# sch.net
KiCad netlist of a schematic drawn in Altium Designer
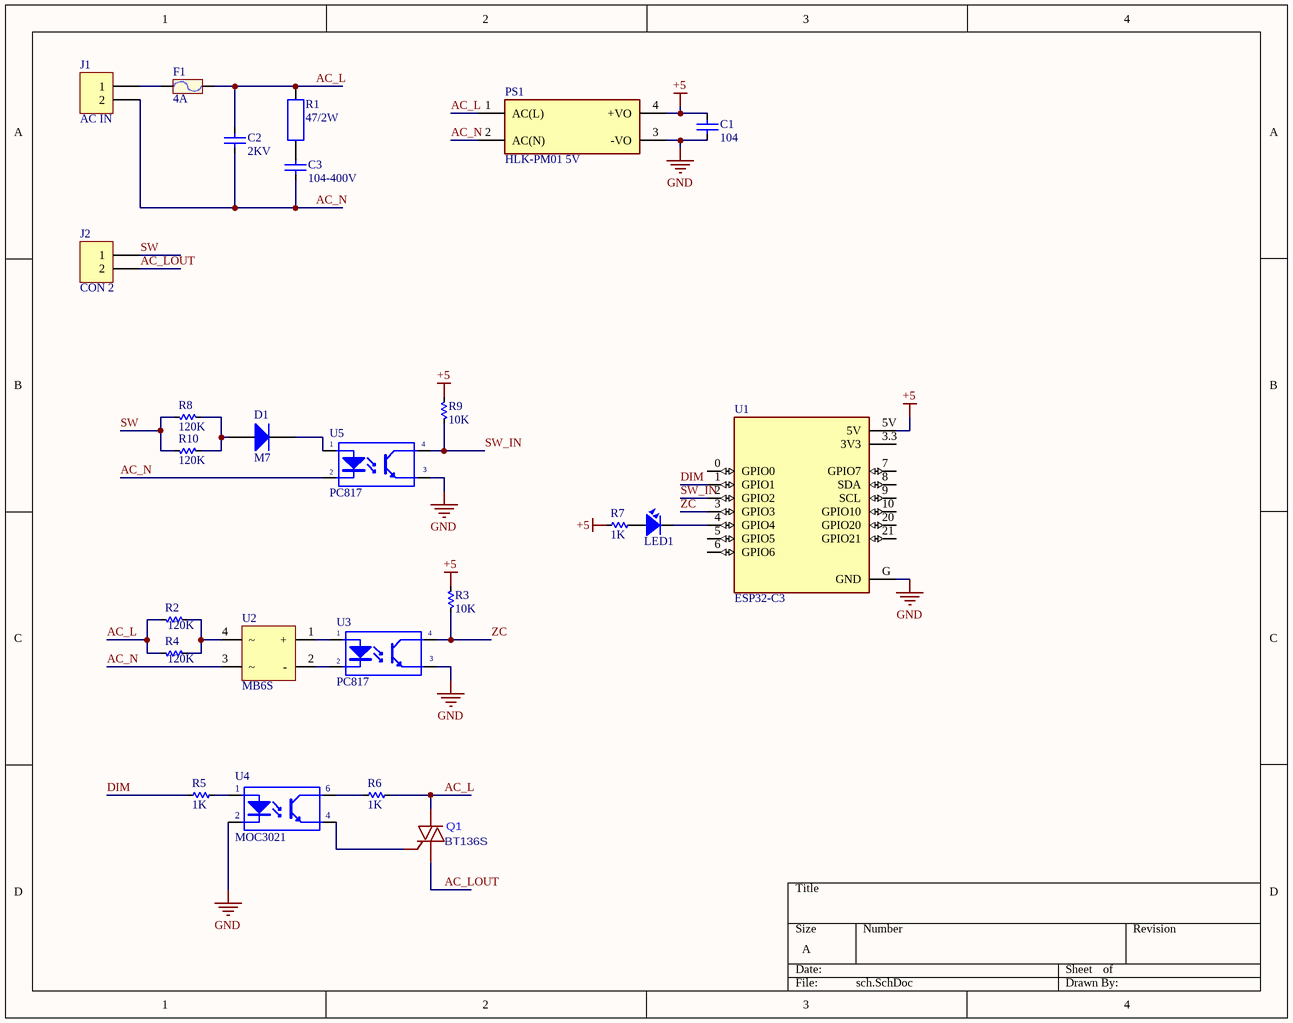
[diagram p0: sch.SchDoc]

(export (version "E")
  (design (tool "Eeschema 10.0.6"))
  (components
    (comp (ref "C1")
      (value "104")
      (footprint "cap 0805")
      (description "Capacitor")
      (libsource (lib "iuh-thuc-hanh") (part "CN"))
    )
    (comp (ref "C2")
      (value "2KV")
      (footprint "Cap 7.5mm")
      (description "Capacitor Ceramic 2KV")
      (libsource (lib "iuh-thuc-hanh") (part "Cap 103 2KV"))
    )
    (comp (ref "C3")
      (value "104-400V")
      (footprint "Cap 10mm")
      (description "Capacitor")
      (libsource (lib "iuh-thuc-hanh") (part "CN"))
    )
    (comp (ref "D1")
      (value "M7")
      (footprint "DIODE SMA")
      (description "Dán")
      (libsource (lib "Altium_Lib_by_KhueNguyenCreator") (part "Diode M7 ( 4007 )"))
    )
    (comp (ref "F1")
      (value "4A")
      (footprint "Fuse rectangular")
      (description "Fuse")
      (fields (field (name "DESIGNED BY") "VanDungEvn"))
      (libsource (lib "iuh-thuc-hanh") (part "Fuse"))
    )
    (comp (ref "J1")
      (value "AC IN")
      (footprint "CON 2 2EDG5.08 B")
      (description "CON2 KF terminal")
      (libsource (lib "iuh-thuc-hanh") (part "CON 2 EDG"))
    )
    (comp (ref "J2")
      (value "CON 2")
      (footprint "CON 2 2EDG5.08 B")
      (description "CON2 KF terminal")
      (libsource (lib "iuh-thuc-hanh") (part "CON 2 EDG"))
    )
    (comp (ref "LED1")
      (value "LED")
      (footprint "LED-0805-Blue")
      (libsource (lib "LIBRARY1") (part "LED SMD"))
    )
    (comp (ref "PS1")
      (value "HLK-PM01 5V")
      (footprint "CONV_HLK-PM01-3W")
      (description "220VAC to 5V")
      (libsource (lib "iuh-thuc-hanh") (part "CONV HLK-PM01"))
    )
    (comp (ref "Q1")
      (value "BT136S")
      (footprint "TO-252-3_L6.6-W6.1-P4.57-LS9.9-BR-CW")
      (libsource (lib "Altium_Lib_by_KhueNguyenCreator") (part "BT136-800E_C2901010"))
    )
    (comp (ref "R1")
      (value "47/2W")
      (footprint "R2WD")
      (description "Resistor 2W")
      (libsource (lib "iuh-thuc-hanh") (part "R2W"))
    )
    (comp (ref "R2")
      (value "120K")
      (footprint "RES-SMD-1210")
      (description "Resistor")
      (fields
        (field (name "MANUFACTURER") "Generic Components")
        (field (name "PUBLISHER") "Altium Hobart Technology Centre")
      )
      (libsource (lib "LIBRARY1") (part "Res-SMD"))
    )
    (comp (ref "R3")
      (value "10K")
      (footprint "RES-SMD-0805")
      (description "Resistor")
      (fields
        (field (name "MANUFACTURER") "Generic Components")
        (field (name "PUBLISHER") "Altium Hobart Technology Centre")
      )
      (libsource (lib "LIBRARY1") (part "Res-SMD"))
    )
    (comp (ref "R4")
      (value "120K")
      (footprint "RES-SMD-1210")
      (description "Resistor")
      (fields
        (field (name "MANUFACTURER") "Generic Components")
        (field (name "PUBLISHER") "Altium Hobart Technology Centre")
      )
      (libsource (lib "LIBRARY1") (part "Res-SMD"))
    )
    (comp (ref "R5")
      (value "1K")
      (footprint "RES-SMD-0805")
      (description "Resistor")
      (fields
        (field (name "MANUFACTURER") "Generic Components")
        (field (name "PUBLISHER") "Altium Hobart Technology Centre")
      )
      (libsource (lib "LIBRARY1") (part "Res-SMD"))
    )
    (comp (ref "R6")
      (value "1K")
      (footprint "RES-SMD-0805")
      (description "Resistor")
      (fields
        (field (name "MANUFACTURER") "Generic Components")
        (field (name "PUBLISHER") "Altium Hobart Technology Centre")
      )
      (libsource (lib "LIBRARY1") (part "Res-SMD"))
    )
    (comp (ref "R7")
      (value "1K")
      (footprint "RES-SMD-0805")
      (description "Resistor")
      (fields
        (field (name "MANUFACTURER") "Generic Components")
        (field (name "PUBLISHER") "Altium Hobart Technology Centre")
      )
      (libsource (lib "LIBRARY1") (part "Res-SMD"))
    )
    (comp (ref "R8")
      (value "120K")
      (footprint "RES-SMD-1210")
      (description "Resistor")
      (fields
        (field (name "MANUFACTURER") "Generic Components")
        (field (name "PUBLISHER") "Altium Hobart Technology Centre")
      )
      (libsource (lib "LIBRARY1") (part "Res-SMD"))
    )
    (comp (ref "R9")
      (value "10K")
      (footprint "RES-SMD-0805")
      (description "Resistor")
      (fields
        (field (name "MANUFACTURER") "Generic Components")
        (field (name "PUBLISHER") "Altium Hobart Technology Centre")
      )
      (libsource (lib "LIBRARY1") (part "Res-SMD"))
    )
    (comp (ref "R10")
      (value "120K")
      (footprint "RES-SMD-1210")
      (description "Resistor")
      (fields
        (field (name "MANUFACTURER") "Generic Components")
        (field (name "PUBLISHER") "Altium Hobart Technology Centre")
      )
      (libsource (lib "LIBRARY1") (part "Res-SMD"))
    )
    (comp (ref "U1")
      (value "ESP32-C3")
      (footprint "ESP32-C3-SMD")
      (libsource (lib "iuh-thuc-hanh") (part "ESP32-C3"))
    )
    (comp (ref "U2")
      (value "MB6S")
      (footprint "TO269AA")
      (description "Bridge Rectifier")
      (libsource (lib "iuh-thuc-hanh") (part "MB6S"))
    )
    (comp (ref "U3")
      (value "PC817")
      (footprint "SOP4")
      (description "Single Opto")
      (libsource (lib "Altium_Lib_by_KhueNguyenCreator") (part "OPTO PC817 SMD"))
    )
    (comp (ref "U4")
      (value "MOC3021")
      (footprint "SO6")
      (description "Single Opto")
      (libsource (lib "LIBRARY1") (part "MOC3021"))
    )
    (comp (ref "U5")
      (value "PC817")
      (footprint "SOP4")
      (description "Single Opto")
      (libsource (lib "Altium_Lib_by_KhueNguyenCreator") (part "OPTO PC817 SMD"))
    )
  )
  (nets
    (net (code "1") (name "+5") (class "Default")
      (node (ref "C1") (pin "1") (pinfunction "1_1") (pintype "passive"))
      (node (ref "PS1") (pin "4") (pinfunction "+VO_4") (pintype "power_in"))
      (node (ref "R3") (pin "1") (pinfunction "1_1") (pintype "passive"))
      (node (ref "R7") (pin "2") (pinfunction "2_2") (pintype "passive"))
      (node (ref "R9") (pin "1") (pinfunction "1_1") (pintype "passive"))
      (node (ref "U1") (pin "5V") (pinfunction "5V_5V") (pintype "power_in"))
    )
    (net (code "2") (name "/AC_L") (class "Default")
      (node (ref "C2") (pin "2") (pinfunction "2_2") (pintype "passive"))
      (node (ref "F1") (pin "2") (pinfunction "2_2") (pintype "passive"))
      (node (ref "PS1") (pin "1") (pinfunction "AC(L)_1") (pintype "power_in"))
      (node (ref "Q1") (pin "2") (pinfunction "T2_2") (pintype "passive"))
      (node (ref "R1") (pin "2") (pinfunction "2_2") (pintype "passive"))
      (node (ref "R2") (pin "1") (pinfunction "1_1") (pintype "passive"))
      (node (ref "R4") (pin "1") (pinfunction "1_1") (pintype "passive"))
      (node (ref "R6") (pin "1") (pinfunction "1_1") (pintype "passive"))
    )
    (net (code "3") (name "/AC_LOUT") (class "Default")
      (node (ref "J2") (pin "2") (pinfunction "2_2") (pintype "passive"))
      (node (ref "Q1") (pin "1") (pinfunction "T1_1") (pintype "passive"))
    )
    (net (code "4") (name "/AC_N") (class "Default")
      (node (ref "C2") (pin "1") (pinfunction "1_1") (pintype "passive"))
      (node (ref "C3") (pin "2") (pinfunction "2_2") (pintype "passive"))
      (node (ref "J1") (pin "2") (pinfunction "2_2") (pintype "passive"))
      (node (ref "PS1") (pin "2") (pinfunction "AC(N)_2") (pintype "power_in"))
      (node (ref "U2") (pin "3") (pinfunction "~_3") (pintype "passive"))
      (node (ref "U5") (pin "2") (pinfunction "K_2") (pintype "passive"))
    )
    (net (code "5") (name "/DIM") (class "Default")
      (node (ref "R5") (pin "2") (pinfunction "2_2") (pintype "passive"))
      (node (ref "U1") (pin "1") (pinfunction "GPIO1_1") (pintype "bidirectional"))
    )
    (net (code "6") (name "/SW") (class "Default")
      (node (ref "J2") (pin "1") (pinfunction "1_1") (pintype "passive"))
      (node (ref "R10") (pin "1") (pinfunction "1_1") (pintype "passive"))
      (node (ref "R8") (pin "1") (pinfunction "1_1") (pintype "passive"))
    )
    (net (code "7") (name "/SW_IN") (class "Default")
      (node (ref "R9") (pin "2") (pinfunction "2_2") (pintype "passive"))
      (node (ref "U1") (pin "2") (pinfunction "GPIO2_2") (pintype "bidirectional"))
      (node (ref "U5") (pin "4") (pinfunction "C_4") (pintype "passive"))
    )
    (net (code "8") (name "/ZC") (class "Default")
      (node (ref "R3") (pin "2") (pinfunction "2_2") (pintype "passive"))
      (node (ref "U1") (pin "3") (pinfunction "GPIO3_3") (pintype "bidirectional"))
      (node (ref "U3") (pin "4") (pinfunction "C_4") (pintype "passive"))
    )
    (net (code "9") (name "GND") (class "Default")
      (node (ref "C1") (pin "2") (pinfunction "2_2") (pintype "passive"))
      (node (ref "PS1") (pin "3") (pinfunction "-VO_3") (pintype "power_in"))
      (node (ref "U1") (pin "G") (pinfunction "GND_G") (pintype "power_in"))
      (node (ref "U3") (pin "3") (pinfunction "E_3") (pintype "passive"))
      (node (ref "U4") (pin "2") (pinfunction "K_2") (pintype "passive"))
      (node (ref "U5") (pin "3") (pinfunction "E_3") (pintype "passive"))
    )
    (net (code "10") (name "Net-(C3-Pad1)") (class "Default")
      (node (ref "C3") (pin "1") (pinfunction "1_1") (pintype "passive"))
      (node (ref "R1") (pin "1") (pinfunction "1_1") (pintype "passive"))
    )
    (net (code "11") (name "Net-(D1-A)") (class "Default")
      (node (ref "D1") (pin "1") (pinfunction "A_1") (pintype "passive"))
      (node (ref "R10") (pin "2") (pinfunction "2_2") (pintype "passive"))
      (node (ref "R8") (pin "2") (pinfunction "2_2") (pintype "passive"))
    )
    (net (code "12") (name "Net-(D1-K)") (class "Default")
      (node (ref "D1") (pin "2") (pinfunction "K_2") (pintype "passive"))
      (node (ref "U5") (pin "1") (pinfunction "A_1") (pintype "passive"))
    )
    (net (code "13") (name "Net-(F1-Pad1)") (class "Default")
      (node (ref "F1") (pin "1") (pinfunction "1_1") (pintype "passive"))
      (node (ref "J1") (pin "1") (pinfunction "1_1") (pintype "passive"))
    )
    (net (code "14") (name "Net-(LED1-Pad1)") (class "Default")
      (node (ref "LED1") (pin "1") (pinfunction "1_1") (pintype "passive"))
      (node (ref "R7") (pin "1") (pinfunction "1_1") (pintype "passive"))
    )
    (net (code "15") (name "Net-(Q1-G)") (class "Default")
      (node (ref "Q1") (pin "3") (pinfunction "G_3") (pintype "passive"))
      (node (ref "U4") (pin "4") (pinfunction "E_4") (pintype "passive"))
    )
    (net (code "16") (name "Net-(R2-Pad2)") (class "Default")
      (node (ref "R2") (pin "2") (pinfunction "2_2") (pintype "passive"))
      (node (ref "R4") (pin "2") (pinfunction "2_2") (pintype "passive"))
      (node (ref "U2") (pin "4") (pinfunction "~_4") (pintype "passive"))
    )
    (net (code "17") (name "Net-(U1-GPIO4)") (class "Default")
      (node (ref "LED1") (pin "2") (pinfunction "2_2") (pintype "passive"))
      (node (ref "U1") (pin "4") (pinfunction "GPIO4_4") (pintype "bidirectional"))
    )
    (net (code "18") (name "Net-(U2-+)") (class "Default")
      (node (ref "U2") (pin "1") (pinfunction "+_1") (pintype "passive"))
      (node (ref "U3") (pin "1") (pinfunction "A_1") (pintype "passive"))
    )
    (net (code "19") (name "Net-(U2--)") (class "Default")
      (node (ref "U2") (pin "2") (pinfunction "-_2") (pintype "passive"))
      (node (ref "U3") (pin "2") (pinfunction "K_2") (pintype "passive"))
    )
    (net (code "20") (name "Net-(U4-A)") (class "Default")
      (node (ref "R5") (pin "1") (pinfunction "1_1") (pintype "passive"))
      (node (ref "U4") (pin "1") (pinfunction "A_1") (pintype "passive"))
    )
    (net (code "21") (name "Net-(U4-C)") (class "Default")
      (node (ref "R6") (pin "2") (pinfunction "2_2") (pintype "passive"))
      (node (ref "U4") (pin "6") (pinfunction "C_6") (pintype "passive"))
    )
    (net (code "22") (name "unconnected-(U1-3V3-Pad3.3)") (class "Default")
      (node (ref "U1") (pin "3.3") (pinfunction "3V3_3.3") (pintype "power_in"))
    )
    (net (code "23") (name "unconnected-(U1-GPIO0-Pad0)") (class "Default")
      (node (ref "U1") (pin "0") (pinfunction "GPIO0_0") (pintype "bidirectional"))
    )
    (net (code "24") (name "unconnected-(U1-GPIO5-Pad5)") (class "Default")
      (node (ref "U1") (pin "5") (pinfunction "GPIO5_5") (pintype "bidirectional"))
    )
    (net (code "25") (name "unconnected-(U1-GPIO6-Pad6)") (class "Default")
      (node (ref "U1") (pin "6") (pinfunction "GPIO6_6") (pintype "bidirectional"))
    )
    (net (code "26") (name "unconnected-(U1-GPIO7-Pad7)") (class "Default")
      (node (ref "U1") (pin "7") (pinfunction "GPIO7_7") (pintype "bidirectional"))
    )
    (net (code "27") (name "unconnected-(U1-GPIO10-Pad10)") (class "Default")
      (node (ref "U1") (pin "10") (pinfunction "GPIO10_10") (pintype "bidirectional"))
    )
    (net (code "28") (name "unconnected-(U1-GPIO20-Pad20)") (class "Default")
      (node (ref "U1") (pin "20") (pinfunction "GPIO20_20") (pintype "bidirectional"))
    )
    (net (code "29") (name "unconnected-(U1-GPIO21-Pad21)") (class "Default")
      (node (ref "U1") (pin "21") (pinfunction "GPIO21_21") (pintype "bidirectional"))
    )
    (net (code "30") (name "unconnected-(U1-SCL-Pad9)") (class "Default")
      (node (ref "U1") (pin "9") (pinfunction "SCL_9") (pintype "bidirectional"))
    )
    (net (code "31") (name "unconnected-(U1-SDA-Pad8)") (class "Default")
      (node (ref "U1") (pin "8") (pinfunction "SDA_8") (pintype "bidirectional"))
    )
  )
)
